# ble_test_1.net
KiCad netlist of a schematic drawn in EAGLE
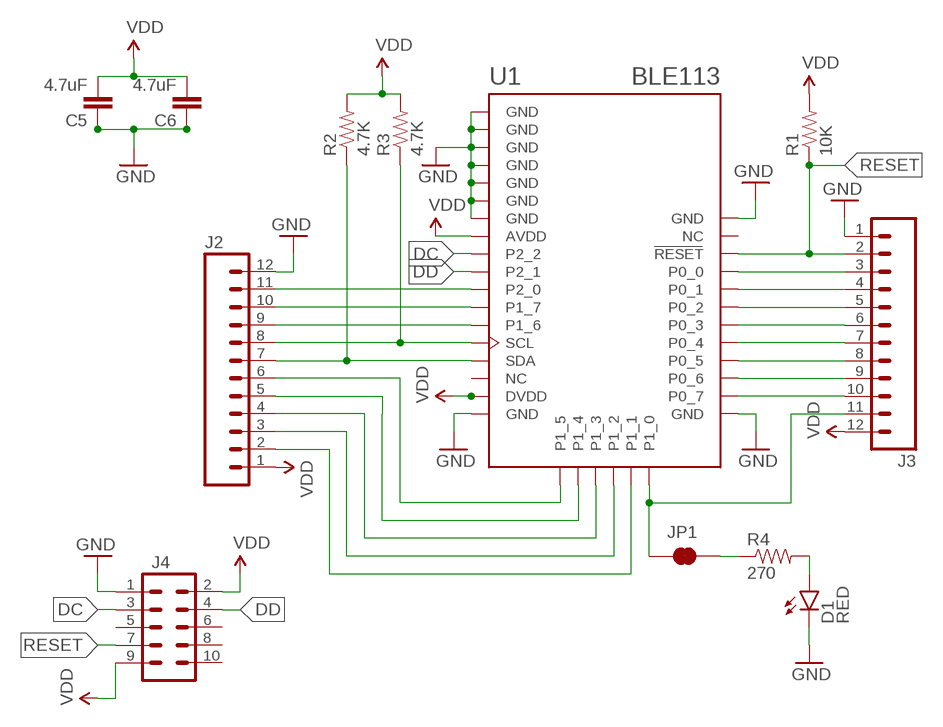
[diagram p0: schematic, sheet 1]

(export (version "E")
  (design (tool "Eeschema 10.0.6"))
  (components
    (comp (ref "C5")
      (value "4.7uF")
      (footprint "eagle-import:0603-CAP")
      (libsource (lib "eagle-import") (part "CAP0603-CAP"))
    )
    (comp (ref "C6")
      (value "4.7uF")
      (footprint "eagle-import:0603-CAP")
      (libsource (lib "eagle-import") (part "CAP0603-CAP"))
    )
    (comp (ref "D1")
      (value "RED")
      (footprint "eagle-import:LED-0603")
      (libsource (lib "eagle-import") (part "LED-RED0603"))
    )
    (comp (ref "J2")
      (value "M12PTH")
      (footprint "eagle-import:1X12")
      (libsource (lib "eagle-import") (part "M12PTH"))
    )
    (comp (ref "J3")
      (value "M12PTH")
      (footprint "eagle-import:1X12")
      (libsource (lib "eagle-import") (part "M12PTH"))
    )
    (comp (ref "J4")
      (value "M05X2PTH")
      (footprint "eagle-import:AVR_ICSP")
      (libsource (lib "eagle-import") (part "M05X2PTH"))
    )
    (comp (ref "JP1")
      (value "JUMPER-PAD-2-NC_BY_TRACE")
      (footprint "eagle-import:PAD-JUMPER-2-NC_BY_TRACE_YES_SILK")
      (libsource (lib "eagle-import") (part "JUMPER-PAD-2-NC_BY_TRACE"))
    )
    (comp (ref "R1")
      (value "10K")
      (footprint "eagle-import:0603-RES")
      (libsource (lib "eagle-import") (part "RESISTOR0603-RES"))
    )
    (comp (ref "R2")
      (value "4.7K")
      (footprint "eagle-import:0603-RES")
      (libsource (lib "eagle-import") (part "RESISTOR0603-RES"))
    )
    (comp (ref "R3")
      (value "4.7K")
      (footprint "eagle-import:0603-RES")
      (libsource (lib "eagle-import") (part "RESISTOR0603-RES"))
    )
    (comp (ref "R4")
      (value "270")
      (footprint "eagle-import:0603-RES")
      (libsource (lib "eagle-import") (part "RESISTOR0603-RES"))
    )
    (comp (ref "U1")
      (value "BLE113")
      (footprint "eagle-import:BLE113-A")
      (libsource (lib "eagle-import") (part "BLE113-VISUAL-A"))
    )
  )
  (nets
    (net (code "1") (name "DC") (class "Default")
      (node (ref "J4") (pin "3") (pinfunction "3_3") (pintype "passive"))
      (node (ref "U1") (pin "P2_2") (pinfunction "P2_2_P2_2") (pintype "bidirectional"))
    )
    (net (code "2") (name "DD") (class "Default")
      (node (ref "J4") (pin "4") (pinfunction "4_4") (pintype "passive"))
      (node (ref "U1") (pin "P2_1") (pinfunction "P2_1_P2_1") (pintype "bidirectional"))
    )
    (net (code "3") (name "GND") (class "Default")
      (node (ref "C5") (pin "1") (pinfunction "1_1") (pintype "passive"))
      (node (ref "C6") (pin "1") (pinfunction "1_1") (pintype "passive"))
      (node (ref "D1") (pin "C") (pinfunction "C_C") (pintype "passive"))
      (node (ref "J2") (pin "12") (pinfunction "12_12") (pintype "passive"))
      (node (ref "J3") (pin "1") (pinfunction "1_1") (pintype "passive"))
      (node (ref "J4") (pin "1") (pinfunction "1_1") (pintype "passive"))
      (node (ref "U1") (pin "GND") (pinfunction "GND_GND") (pintype "power_in"))
      (node (ref "U1") (pin "GND@10") (pinfunction "GND_GND@10") (pintype "power_in"))
      (node (ref "U1") (pin "GND@2") (pinfunction "GND_GND@2") (pintype "power_in"))
      (node (ref "U1") (pin "GND@3") (pinfunction "GND_GND@3") (pintype "power_in"))
      (node (ref "U1") (pin "GND@4") (pinfunction "GND_GND@4") (pintype "power_in"))
      (node (ref "U1") (pin "GND@5") (pinfunction "GND_GND@5") (pintype "power_in"))
      (node (ref "U1") (pin "GND@6") (pinfunction "GND_GND@6") (pintype "power_in"))
      (node (ref "U1") (pin "GND@7") (pinfunction "GND_GND@7") (pintype "power_in"))
      (node (ref "U1") (pin "GND@8") (pinfunction "GND_GND@8") (pintype "power_in"))
      (node (ref "U1") (pin "GND@9") (pinfunction "GND_GND@9") (pintype "power_in"))
    )
    (net (code "4") (name "Net-(D1-PadA)") (class "Default")
      (node (ref "D1") (pin "A") (pinfunction "A_A") (pintype "passive"))
      (node (ref "R4") (pin "2") (pinfunction "2_2") (pintype "passive"))
    )
    (net (code "5") (name "Net-(J2-Pad2)") (class "Default")
      (node (ref "J2") (pin "2") (pinfunction "2_2") (pintype "passive"))
      (node (ref "U1") (pin "P1_1") (pinfunction "P1_1_P1_1") (pintype "bidirectional"))
    )
    (net (code "6") (name "Net-(J2-Pad3)") (class "Default")
      (node (ref "J2") (pin "3") (pinfunction "3_3") (pintype "passive"))
      (node (ref "U1") (pin "P1_2") (pinfunction "P1_2_P1_2") (pintype "bidirectional"))
    )
    (net (code "7") (name "Net-(J2-Pad4)") (class "Default")
      (node (ref "J2") (pin "4") (pinfunction "4_4") (pintype "passive"))
      (node (ref "U1") (pin "P1_3") (pinfunction "P1_3_P1_3") (pintype "bidirectional"))
    )
    (net (code "8") (name "Net-(J2-Pad5)") (class "Default")
      (node (ref "J2") (pin "5") (pinfunction "5_5") (pintype "passive"))
      (node (ref "U1") (pin "P1_4") (pinfunction "P1_4_P1_4") (pintype "bidirectional"))
    )
    (net (code "9") (name "Net-(J2-Pad6)") (class "Default")
      (node (ref "J2") (pin "6") (pinfunction "6_6") (pintype "passive"))
      (node (ref "U1") (pin "P1_5") (pinfunction "P1_5_P1_5") (pintype "bidirectional"))
    )
    (net (code "10") (name "Net-(J2-Pad7)") (class "Default")
      (node (ref "J2") (pin "7") (pinfunction "7_7") (pintype "passive"))
      (node (ref "R2") (pin "1") (pinfunction "1_1") (pintype "passive"))
      (node (ref "U1") (pin "SDA") (pinfunction "SDA_SDA") (pintype "bidirectional"))
    )
    (net (code "11") (name "Net-(J2-Pad8)") (class "Default")
      (node (ref "J2") (pin "8") (pinfunction "8_8") (pintype "passive"))
      (node (ref "R3") (pin "1") (pinfunction "1_1") (pintype "passive"))
      (node (ref "U1") (pin "SCL") (pinfunction "SCL_SCL") (pintype "bidirectional"))
    )
    (net (code "12") (name "Net-(J2-Pad9)") (class "Default")
      (node (ref "J2") (pin "9") (pinfunction "9_9") (pintype "passive"))
      (node (ref "U1") (pin "P1_6") (pinfunction "P1_6_P1_6") (pintype "bidirectional"))
    )
    (net (code "13") (name "Net-(J2-Pad10)") (class "Default")
      (node (ref "J2") (pin "10") (pinfunction "10_10") (pintype "passive"))
      (node (ref "U1") (pin "P1_7") (pinfunction "P1_7_P1_7") (pintype "bidirectional"))
    )
    (net (code "14") (name "Net-(J2-Pad11)") (class "Default")
      (node (ref "J2") (pin "11") (pinfunction "11_11") (pintype "passive"))
      (node (ref "U1") (pin "P2_0") (pinfunction "P2_0_P2_0") (pintype "bidirectional"))
    )
    (net (code "15") (name "Net-(J3-Pad3)") (class "Default")
      (node (ref "J3") (pin "3") (pinfunction "3_3") (pintype "passive"))
      (node (ref "U1") (pin "P0_0") (pinfunction "P0_0_P0_0") (pintype "bidirectional"))
    )
    (net (code "16") (name "Net-(J3-Pad4)") (class "Default")
      (node (ref "J3") (pin "4") (pinfunction "4_4") (pintype "passive"))
      (node (ref "U1") (pin "P0_1") (pinfunction "P0_1_P0_1") (pintype "bidirectional"))
    )
    (net (code "17") (name "Net-(J3-Pad5)") (class "Default")
      (node (ref "J3") (pin "5") (pinfunction "5_5") (pintype "passive"))
      (node (ref "U1") (pin "P0_2") (pinfunction "P0_2_P0_2") (pintype "bidirectional"))
    )
    (net (code "18") (name "Net-(J3-Pad6)") (class "Default")
      (node (ref "J3") (pin "6") (pinfunction "6_6") (pintype "passive"))
      (node (ref "U1") (pin "P0_3") (pinfunction "P0_3_P0_3") (pintype "bidirectional"))
    )
    (net (code "19") (name "Net-(J3-Pad7)") (class "Default")
      (node (ref "J3") (pin "7") (pinfunction "7_7") (pintype "passive"))
      (node (ref "U1") (pin "P0_4") (pinfunction "P0_4_P0_4") (pintype "bidirectional"))
    )
    (net (code "20") (name "Net-(J3-Pad8)") (class "Default")
      (node (ref "J3") (pin "8") (pinfunction "8_8") (pintype "passive"))
      (node (ref "U1") (pin "P0_5") (pinfunction "P0_5_P0_5") (pintype "bidirectional"))
    )
    (net (code "21") (name "Net-(J3-Pad9)") (class "Default")
      (node (ref "J3") (pin "9") (pinfunction "9_9") (pintype "passive"))
      (node (ref "U1") (pin "P0_6") (pinfunction "P0_6_P0_6") (pintype "bidirectional"))
    )
    (net (code "22") (name "Net-(J3-Pad10)") (class "Default")
      (node (ref "J3") (pin "10") (pinfunction "10_10") (pintype "passive"))
      (node (ref "U1") (pin "P0_7") (pinfunction "P0_7_P0_7") (pintype "bidirectional"))
    )
    (net (code "23") (name "Net-(J3-Pad11)") (class "Default")
      (node (ref "J3") (pin "11") (pinfunction "11_11") (pintype "passive"))
      (node (ref "JP1") (pin "1") (pinfunction "1_1") (pintype "passive"))
      (node (ref "U1") (pin "P1_0") (pinfunction "P1_0_P1_0") (pintype "bidirectional"))
    )
    (net (code "24") (name "Net-(JP1-Pad2)") (class "Default")
      (node (ref "JP1") (pin "2") (pinfunction "2_2") (pintype "passive"))
      (node (ref "R4") (pin "1") (pinfunction "1_1") (pintype "passive"))
    )
    (net (code "25") (name "RESET") (class "Default")
      (node (ref "J3") (pin "2") (pinfunction "2_2") (pintype "passive"))
      (node (ref "J4") (pin "7") (pinfunction "7_7") (pintype "passive"))
      (node (ref "R1") (pin "1") (pinfunction "1_1") (pintype "passive"))
      (node (ref "U1") (pin "RESET") (pinfunction "RESET_RESET") (pintype "input"))
    )
    (net (code "26") (name "VDD") (class "Default")
      (node (ref "C5") (pin "2") (pinfunction "2_2") (pintype "passive"))
      (node (ref "C6") (pin "2") (pinfunction "2_2") (pintype "passive"))
      (node (ref "J2") (pin "1") (pinfunction "1_1") (pintype "passive"))
      (node (ref "J3") (pin "12") (pinfunction "12_12") (pintype "passive"))
      (node (ref "J4") (pin "2") (pinfunction "2_2") (pintype "passive"))
      (node (ref "J4") (pin "9") (pinfunction "9_9") (pintype "passive"))
      (node (ref "R1") (pin "2") (pinfunction "2_2") (pintype "passive"))
      (node (ref "R2") (pin "2") (pinfunction "2_2") (pintype "passive"))
      (node (ref "R3") (pin "2") (pinfunction "2_2") (pintype "passive"))
      (node (ref "U1") (pin "AVDD") (pinfunction "AVDD_AVDD") (pintype "power_in"))
      (node (ref "U1") (pin "DVDD") (pinfunction "DVDD_DVDD") (pintype "power_in"))
    )
    (net (code "27") (name "unconnected-(J4-Pad5)") (class "Default")
      (node (ref "J4") (pin "5") (pinfunction "5_5") (pintype "passive"))
    )
    (net (code "28") (name "unconnected-(J4-Pad6)") (class "Default")
      (node (ref "J4") (pin "6") (pinfunction "6_6") (pintype "passive"))
    )
    (net (code "29") (name "unconnected-(J4-Pad8)") (class "Default")
      (node (ref "J4") (pin "8") (pinfunction "8_8") (pintype "passive"))
    )
    (net (code "30") (name "unconnected-(J4-Pad10)") (class "Default")
      (node (ref "J4") (pin "10") (pinfunction "10_10") (pintype "passive"))
    )
    (net (code "31") (name "unconnected-(U1-NC-PadNC@2)") (class "Default")
      (node (ref "U1") (pin "NC@2") (pinfunction "NC_NC@2") (pintype "no_connect"))
    )
    (net (code "32") (name "unconnected-(U1-PadNC)") (class "Default")
      (node (ref "U1") (pin "NC") (pinfunction "NC_NC") (pintype "no_connect"))
    )
  )
)
